# CONNDIN96.net
KiCad netlist of a schematic drawn in Altium Designer
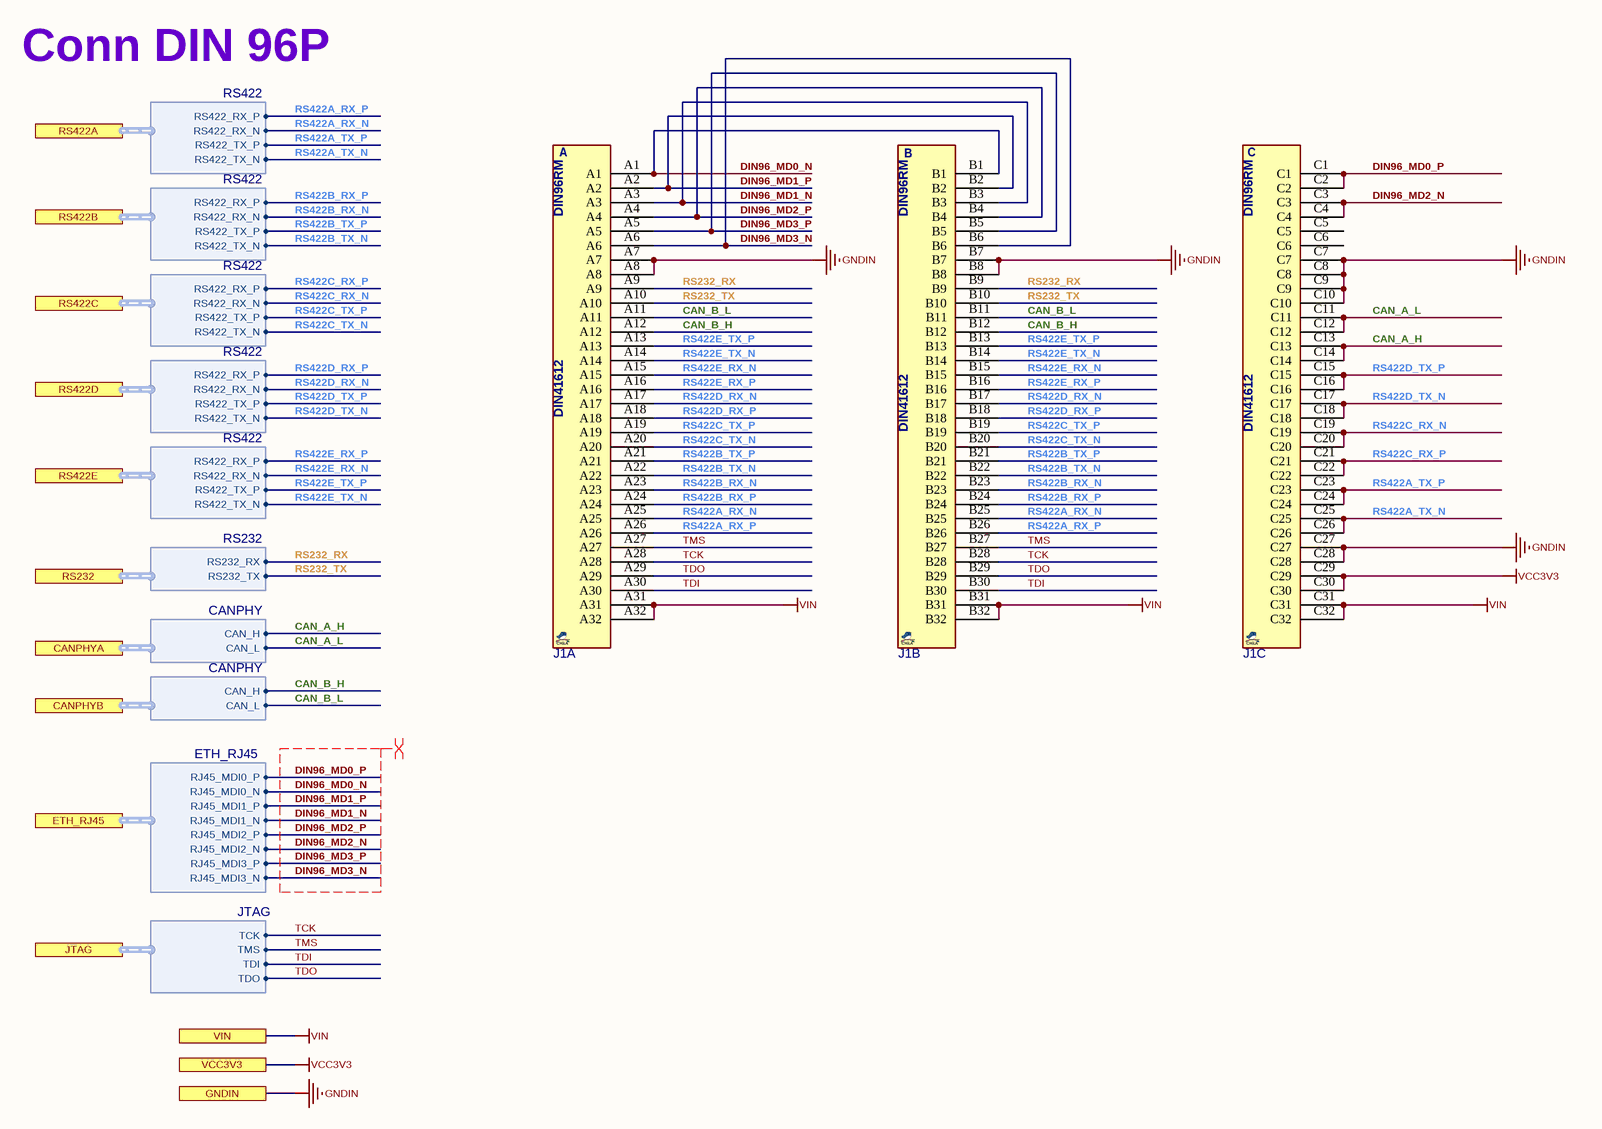
[diagram p0: CONNDIN96.SchDoc]

(export (version "E")
  (design (tool "Eeschema 10.0.6"))
  (components
    (comp (ref "J1")
      (value "DIN96SM")
      (footprint "DIN_96SM")
      (description "DIN 41612, 2.54mm,pin,DIN 41612,solder,PCB,96w,")
      (fields (field (name "MANF") "TE") (field (name "MANF_P#") "650470-5"))
      (libsource (lib "conn_b2b") (part "DIN41612_96SM"))
    )
  )
  (nets
    (net (code "6") (name "/CAN_A_H") (class "Default")
      (node (ref "J1") (pin "C13") (pinfunction "C13_C13") (pintype "passive"))
      (node (ref "J1") (pin "C14") (pinfunction "C14_C14") (pintype "passive"))
    )
    (net (code "7") (name "/CAN_A_L") (class "Default")
      (node (ref "J1") (pin "C11") (pinfunction "C11_C11") (pintype "passive"))
      (node (ref "J1") (pin "C12") (pinfunction "C12_C12") (pintype "passive"))
    )
    (net (code "8") (name "/CAN_B_H") (class "Default")
      (node (ref "J1") (pin "A12") (pinfunction "A12_A12") (pintype "passive"))
      (node (ref "J1") (pin "B12") (pinfunction "B12_B12") (pintype "passive"))
    )
    (net (code "9") (name "/CAN_B_L") (class "Default")
      (node (ref "J1") (pin "A11") (pinfunction "A11_A11") (pintype "passive"))
      (node (ref "J1") (pin "B11") (pinfunction "B11_B11") (pintype "passive"))
    )
    (net (code "10") (name "/DIN96_MD0_N") (class "Default")
      (node (ref "J1") (pin "A1") (pinfunction "A1_A1") (pintype "passive"))
      (node (ref "J1") (pin "B1") (pinfunction "B1_B1") (pintype "passive"))
    )
    (net (code "11") (name "/DIN96_MD0_P") (class "Default")
      (node (ref "J1") (pin "C1") (pinfunction "C1_C1") (pintype "passive"))
      (node (ref "J1") (pin "C2") (pinfunction "C2_C2") (pintype "passive"))
    )
    (net (code "12") (name "/DIN96_MD1_N") (class "Default")
      (node (ref "J1") (pin "A3") (pinfunction "A3_A3") (pintype "passive"))
      (node (ref "J1") (pin "B3") (pinfunction "B3_B3") (pintype "passive"))
    )
    (net (code "13") (name "/DIN96_MD1_P") (class "Default")
      (node (ref "J1") (pin "A2") (pinfunction "A2_A2") (pintype "passive"))
      (node (ref "J1") (pin "B2") (pinfunction "B2_B2") (pintype "passive"))
    )
    (net (code "14") (name "/DIN96_MD2_N") (class "Default")
      (node (ref "J1") (pin "C3") (pinfunction "C3_C3") (pintype "passive"))
      (node (ref "J1") (pin "C4") (pinfunction "C4_C4") (pintype "passive"))
    )
    (net (code "15") (name "/DIN96_MD2_P") (class "Default")
      (node (ref "J1") (pin "A4") (pinfunction "A4_A4") (pintype "passive"))
      (node (ref "J1") (pin "B4") (pinfunction "B4_B4") (pintype "passive"))
    )
    (net (code "16") (name "/DIN96_MD3_N") (class "Default")
      (node (ref "J1") (pin "A6") (pinfunction "A6_A6") (pintype "passive"))
      (node (ref "J1") (pin "B6") (pinfunction "B6_B6") (pintype "passive"))
    )
    (net (code "17") (name "/DIN96_MD3_P") (class "Default")
      (node (ref "J1") (pin "A5") (pinfunction "A5_A5") (pintype "passive"))
      (node (ref "J1") (pin "B5") (pinfunction "B5_B5") (pintype "passive"))
    )
    (net (code "18") (name "/RS232_RX") (class "Default")
      (node (ref "J1") (pin "A9") (pinfunction "A9_A9") (pintype "passive"))
      (node (ref "J1") (pin "B9") (pinfunction "B9_B9") (pintype "passive"))
    )
    (net (code "19") (name "/RS232_TX") (class "Default")
      (node (ref "J1") (pin "A10") (pinfunction "A10_A10") (pintype "passive"))
      (node (ref "J1") (pin "B10") (pinfunction "B10_B10") (pintype "passive"))
    )
    (net (code "20") (name "/RS422A_RX_N") (class "Default")
      (node (ref "J1") (pin "A25") (pinfunction "A25_A25") (pintype "passive"))
      (node (ref "J1") (pin "B25") (pinfunction "B25_B25") (pintype "passive"))
    )
    (net (code "21") (name "/RS422A_RX_P") (class "Default")
      (node (ref "J1") (pin "A26") (pinfunction "A26_A26") (pintype "passive"))
      (node (ref "J1") (pin "B26") (pinfunction "B26_B26") (pintype "passive"))
    )
    (net (code "22") (name "/RS422A_TX_N") (class "Default")
      (node (ref "J1") (pin "C25") (pinfunction "C25_C25") (pintype "passive"))
      (node (ref "J1") (pin "C26") (pinfunction "C26_C26") (pintype "passive"))
    )
    (net (code "23") (name "/RS422A_TX_P") (class "Default")
      (node (ref "J1") (pin "C23") (pinfunction "C23_C23") (pintype "passive"))
      (node (ref "J1") (pin "C24") (pinfunction "C24_C24") (pintype "passive"))
    )
    (net (code "24") (name "/RS422B_RX_N") (class "Default")
      (node (ref "J1") (pin "A23") (pinfunction "A23_A23") (pintype "passive"))
      (node (ref "J1") (pin "B23") (pinfunction "B23_B23") (pintype "passive"))
    )
    (net (code "25") (name "/RS422B_RX_P") (class "Default")
      (node (ref "J1") (pin "A24") (pinfunction "A24_A24") (pintype "passive"))
      (node (ref "J1") (pin "B24") (pinfunction "B24_B24") (pintype "passive"))
    )
    (net (code "26") (name "/RS422B_TX_N") (class "Default")
      (node (ref "J1") (pin "A22") (pinfunction "A22_A22") (pintype "passive"))
      (node (ref "J1") (pin "B22") (pinfunction "B22_B22") (pintype "passive"))
    )
    (net (code "27") (name "/RS422B_TX_P") (class "Default")
      (node (ref "J1") (pin "A21") (pinfunction "A21_A21") (pintype "passive"))
      (node (ref "J1") (pin "B21") (pinfunction "B21_B21") (pintype "passive"))
    )
    (net (code "28") (name "/RS422C_RX_N") (class "Default")
      (node (ref "J1") (pin "C19") (pinfunction "C19_C19") (pintype "passive"))
      (node (ref "J1") (pin "C20") (pinfunction "C20_C20") (pintype "passive"))
    )
    (net (code "29") (name "/RS422C_RX_P") (class "Default")
      (node (ref "J1") (pin "C21") (pinfunction "C21_C21") (pintype "passive"))
      (node (ref "J1") (pin "C22") (pinfunction "C22_C22") (pintype "passive"))
    )
    (net (code "30") (name "/RS422C_TX_N") (class "Default")
      (node (ref "J1") (pin "A20") (pinfunction "A20_A20") (pintype "passive"))
      (node (ref "J1") (pin "B20") (pinfunction "B20_B20") (pintype "passive"))
    )
    (net (code "31") (name "/RS422C_TX_P") (class "Default")
      (node (ref "J1") (pin "A19") (pinfunction "A19_A19") (pintype "passive"))
      (node (ref "J1") (pin "B19") (pinfunction "B19_B19") (pintype "passive"))
    )
    (net (code "32") (name "/RS422D_RX_N") (class "Default")
      (node (ref "J1") (pin "A17") (pinfunction "A17_A17") (pintype "passive"))
      (node (ref "J1") (pin "B17") (pinfunction "B17_B17") (pintype "passive"))
    )
    (net (code "33") (name "/RS422D_RX_P") (class "Default")
      (node (ref "J1") (pin "A18") (pinfunction "A18_A18") (pintype "passive"))
      (node (ref "J1") (pin "B18") (pinfunction "B18_B18") (pintype "passive"))
    )
    (net (code "34") (name "/RS422D_TX_N") (class "Default")
      (node (ref "J1") (pin "C17") (pinfunction "C17_C17") (pintype "passive"))
      (node (ref "J1") (pin "C18") (pinfunction "C18_C18") (pintype "passive"))
    )
    (net (code "35") (name "/RS422D_TX_P") (class "Default")
      (node (ref "J1") (pin "C15") (pinfunction "C15_C15") (pintype "passive"))
      (node (ref "J1") (pin "C16") (pinfunction "C16_C16") (pintype "passive"))
    )
    (net (code "36") (name "/RS422E_RX_N") (class "Default")
      (node (ref "J1") (pin "A15") (pinfunction "A15_A15") (pintype "passive"))
      (node (ref "J1") (pin "B15") (pinfunction "B15_B15") (pintype "passive"))
    )
    (net (code "37") (name "/RS422E_RX_P") (class "Default")
      (node (ref "J1") (pin "A16") (pinfunction "A16_A16") (pintype "passive"))
      (node (ref "J1") (pin "B16") (pinfunction "B16_B16") (pintype "passive"))
    )
    (net (code "38") (name "/RS422E_TX_N") (class "Default")
      (node (ref "J1") (pin "A14") (pinfunction "A14_A14") (pintype "passive"))
      (node (ref "J1") (pin "B14") (pinfunction "B14_B14") (pintype "passive"))
    )
    (net (code "39") (name "/RS422E_TX_P") (class "Default")
      (node (ref "J1") (pin "A13") (pinfunction "A13_A13") (pintype "passive"))
      (node (ref "J1") (pin "B13") (pinfunction "B13_B13") (pintype "passive"))
    )
    (net (code "40") (name "/TCK") (class "Default")
      (node (ref "J1") (pin "A28") (pinfunction "A28_A28") (pintype "passive"))
      (node (ref "J1") (pin "B28") (pinfunction "B28_B28") (pintype "passive"))
    )
    (net (code "41") (name "/TDI") (class "Default")
      (node (ref "J1") (pin "A30") (pinfunction "A30_A30") (pintype "passive"))
      (node (ref "J1") (pin "B30") (pinfunction "B30_B30") (pintype "passive"))
    )
    (net (code "42") (name "/TDO") (class "Default")
      (node (ref "J1") (pin "A29") (pinfunction "A29_A29") (pintype "passive"))
      (node (ref "J1") (pin "B29") (pinfunction "B29_B29") (pintype "passive"))
    )
    (net (code "43") (name "/TMS") (class "Default")
      (node (ref "J1") (pin "A27") (pinfunction "A27_A27") (pintype "passive"))
      (node (ref "J1") (pin "B27") (pinfunction "B27_B27") (pintype "passive"))
    )
    (net (code "49") (name "GNDIN") (class "Default")
      (node (ref "J1") (pin "A7") (pinfunction "A7_A7") (pintype "passive"))
      (node (ref "J1") (pin "A8") (pinfunction "A8_A8") (pintype "passive"))
      (node (ref "J1") (pin "B7") (pinfunction "B7_B7") (pintype "passive"))
      (node (ref "J1") (pin "B8") (pinfunction "B8_B8") (pintype "passive"))
      (node (ref "J1") (pin "C10") (pinfunction "C10_C10") (pintype "passive"))
      (node (ref "J1") (pin "C27") (pinfunction "C27_C27") (pintype "passive"))
      (node (ref "J1") (pin "C28") (pinfunction "C28_C28") (pintype "passive"))
      (node (ref "J1") (pin "C7") (pinfunction "C7_C7") (pintype "passive"))
      (node (ref "J1") (pin "C8") (pinfunction "C8_C8") (pintype "passive"))
      (node (ref "J1") (pin "C9") (pinfunction "C9_C9") (pintype "passive"))
    )
    (net (code "50") (name "VCC3V3") (class "Default")
      (node (ref "J1") (pin "C29") (pinfunction "C29_C29") (pintype "passive"))
      (node (ref "J1") (pin "C30") (pinfunction "C30_C30") (pintype "passive"))
    )
    (net (code "51") (name "VIN") (class "Default")
      (node (ref "J1") (pin "A31") (pinfunction "A31_A31") (pintype "passive"))
      (node (ref "J1") (pin "A32") (pinfunction "A32_A32") (pintype "passive"))
      (node (ref "J1") (pin "B31") (pinfunction "B31_B31") (pintype "passive"))
      (node (ref "J1") (pin "B32") (pinfunction "B32_B32") (pintype "passive"))
      (node (ref "J1") (pin "C31") (pinfunction "C31_C31") (pintype "passive"))
      (node (ref "J1") (pin "C32") (pinfunction "C32_C32") (pintype "passive"))
    )
    (net (code "52") (name "unconnected-(J1-PadC5)") (class "Default")
      (node (ref "J1") (pin "C5") (pinfunction "C5_C5") (pintype "passive"))
    )
    (net (code "53") (name "unconnected-(J1-PadC6)") (class "Default")
      (node (ref "J1") (pin "C6") (pinfunction "C6_C6") (pintype "passive"))
    )
  )
)
